# decoupling.net
KiCad netlist of a schematic drawn in Altium Designer
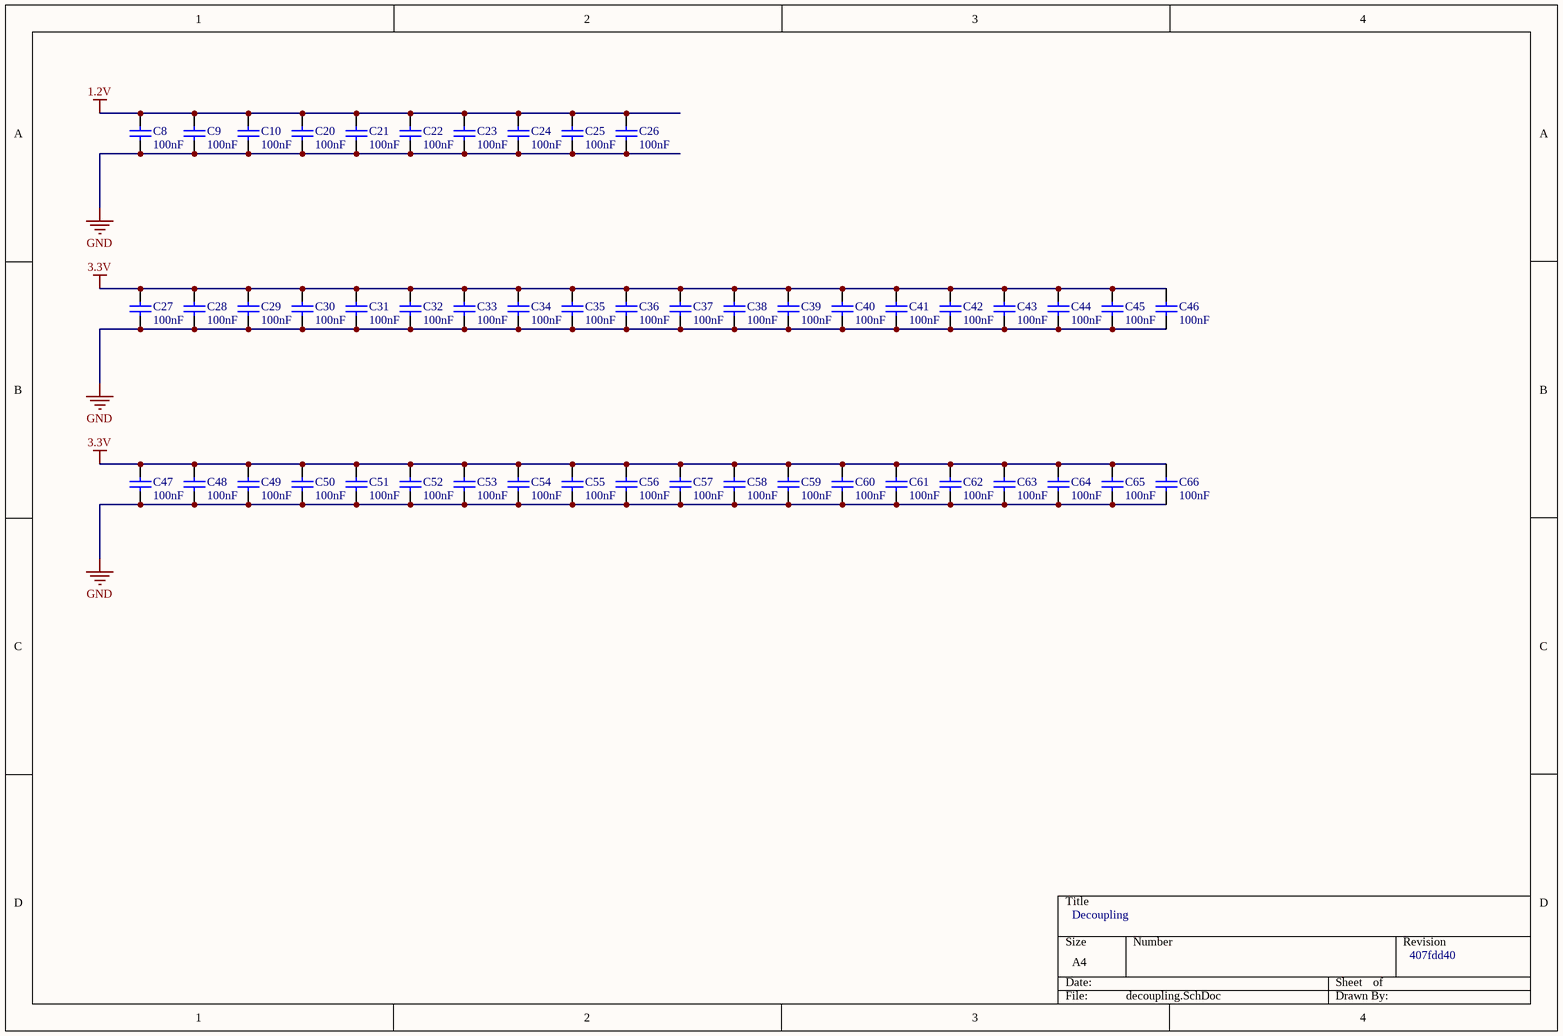
[diagram p0: decoupling.SchDoc]

(export (version "E")
  (design (tool "Eeschema 10.0.6"))
  (components
    (comp (ref "C8")
      (value "100nF")
      (footprint "CAPC1210(3225)100_L")
      (description "CAP 100nF 100V ±0.25pF 1210 (3225 Metric) Thickness 1mm SMD")
      (fields (field (name "TOLERANCE") "±0.25pF") (field (name "Comment") "CAP 10pF 100V 1210(3225)"))
      (libsource (lib "Altium Content Vault") (part "CMP-1038-00005-1"))
    )
    (comp (ref "C9")
      (value "100nF")
      (footprint "CAPC1210(3225)100_L")
      (description "CAP 100nF 100V ±0.25pF 1210 (3225 Metric) Thickness 1mm SMD")
      (fields (field (name "TOLERANCE") "±0.25pF") (field (name "Comment") "CAP 10pF 100V 1210(3225)"))
      (libsource (lib "Altium Content Vault") (part "CMP-1038-00005-1"))
    )
    (comp (ref "C10")
      (value "100nF")
      (footprint "CAPC1210(3225)100_L")
      (description "CAP 100nF 100V ±0.25pF 1210 (3225 Metric) Thickness 1mm SMD")
      (fields (field (name "TOLERANCE") "±0.25pF") (field (name "Comment") "CAP 10pF 100V 1210(3225)"))
      (libsource (lib "Altium Content Vault") (part "CMP-1038-00005-1"))
    )
    (comp (ref "C20")
      (value "100nF")
      (footprint "CAPC1210(3225)100_L")
      (description "CAP 100nF 100V ±0.25pF 1210 (3225 Metric) Thickness 1mm SMD")
      (fields (field (name "TOLERANCE") "±0.25pF") (field (name "Comment") "CAP 100nF 100V 1210(3225)"))
      (libsource (lib "Altium Content Vault") (part "CMP-1038-00005-1"))
    )
    (comp (ref "C21")
      (value "100nF")
      (footprint "CAPC1210(3225)100_L")
      (description "CAP 100nF 100V ±0.25pF 1210 (3225 Metric) Thickness 1mm SMD")
      (fields (field (name "TOLERANCE") "±0.25pF") (field (name "Comment") "CAP 100nF 100V 1210(3225)"))
      (libsource (lib "Altium Content Vault") (part "CMP-1038-00005-1"))
    )
    (comp (ref "C22")
      (value "100nF")
      (footprint "CAPC1210(3225)100_L")
      (description "CAP 100nF 100V ±0.25pF 1210 (3225 Metric) Thickness 1mm SMD")
      (fields (field (name "TOLERANCE") "±0.25pF") (field (name "Comment") "CAP 100nF 100V 1210(3225)"))
      (libsource (lib "Altium Content Vault") (part "CMP-1038-00005-1"))
    )
    (comp (ref "C23")
      (value "100nF")
      (footprint "CAPC1210(3225)100_L")
      (description "CAP 100nF 100V ±0.25pF 1210 (3225 Metric) Thickness 1mm SMD")
      (fields (field (name "TOLERANCE") "±0.25pF") (field (name "Comment") "CAP 100nF 100V 1210(3225)"))
      (libsource (lib "Altium Content Vault") (part "CMP-1038-00005-1"))
    )
    (comp (ref "C24")
      (value "100nF")
      (footprint "CAPC1210(3225)100_L")
      (description "CAP 100nF 100V ±0.25pF 1210 (3225 Metric) Thickness 1mm SMD")
      (fields (field (name "TOLERANCE") "±0.25pF") (field (name "Comment") "CAP 100nF 100V 1210(3225)"))
      (libsource (lib "Altium Content Vault") (part "CMP-1038-00005-1"))
    )
    (comp (ref "C25")
      (value "100nF")
      (footprint "CAPC1210(3225)100_L")
      (description "CAP 100nF 100V ±0.25pF 1210 (3225 Metric) Thickness 1mm SMD")
      (fields (field (name "TOLERANCE") "±0.25pF") (field (name "Comment") "CAP 100nF 100V 1210(3225)"))
      (libsource (lib "Altium Content Vault") (part "CMP-1038-00005-1"))
    )
    (comp (ref "C26")
      (value "100nF")
      (footprint "CAPC1210(3225)100_L")
      (description "CAP 100nF 100V ±0.25pF 1210 (3225 Metric) Thickness 1mm SMD")
      (fields (field (name "TOLERANCE") "±0.25pF") (field (name "Comment") "CAP 100nF 100V 1210(3225)"))
      (libsource (lib "Altium Content Vault") (part "CMP-1038-00005-1"))
    )
    (comp (ref "C27")
      (value "100nF")
      (footprint "CAPC1210(3225)100_L")
      (description "CAP 100nF 100V ±0.25pF 1210 (3225 Metric) Thickness 1mm SMD")
      (fields (field (name "TOLERANCE") "±0.25pF") (field (name "Comment") "CAP 100nF 100V 1210(3225)"))
      (libsource (lib "Altium Content Vault") (part "CMP-1038-00005-1"))
    )
    (comp (ref "C28")
      (value "100nF")
      (footprint "CAPC1210(3225)100_L")
      (description "CAP 100nF 100V ±0.25pF 1210 (3225 Metric) Thickness 1mm SMD")
      (fields (field (name "TOLERANCE") "±0.25pF") (field (name "Comment") "CAP 100nF 100V 1210(3225)"))
      (libsource (lib "Altium Content Vault") (part "CMP-1038-00005-1"))
    )
    (comp (ref "C29")
      (value "100nF")
      (footprint "CAPC1210(3225)100_L")
      (description "CAP 100nF 100V ±0.25pF 1210 (3225 Metric) Thickness 1mm SMD")
      (fields (field (name "TOLERANCE") "±0.25pF") (field (name "Comment") "CAP 100nF 100V 1210(3225)"))
      (libsource (lib "Altium Content Vault") (part "CMP-1038-00005-1"))
    )
    (comp (ref "C30")
      (value "100nF")
      (footprint "CAPC1210(3225)100_L")
      (description "CAP 100nF 100V ±0.25pF 1210 (3225 Metric) Thickness 1mm SMD")
      (fields (field (name "TOLERANCE") "±0.25pF") (field (name "Comment") "CAP 100nF 100V 1210(3225)"))
      (libsource (lib "Altium Content Vault") (part "CMP-1038-00005-1"))
    )
    (comp (ref "C31")
      (value "100nF")
      (footprint "CAPC1210(3225)100_L")
      (description "CAP 100nF 100V ±0.25pF 1210 (3225 Metric) Thickness 1mm SMD")
      (fields (field (name "TOLERANCE") "±0.25pF") (field (name "Comment") "CAP 100nF 100V 1210(3225)"))
      (libsource (lib "Altium Content Vault") (part "CMP-1038-00005-1"))
    )
    (comp (ref "C32")
      (value "100nF")
      (footprint "CAPC1210(3225)100_L")
      (description "CAP 100nF 100V ±0.25pF 1210 (3225 Metric) Thickness 1mm SMD")
      (fields (field (name "TOLERANCE") "±0.25pF") (field (name "Comment") "CAP 100nF 100V 1210(3225)"))
      (libsource (lib "Altium Content Vault") (part "CMP-1038-00005-1"))
    )
    (comp (ref "C33")
      (value "100nF")
      (footprint "CAPC1210(3225)100_L")
      (description "CAP 100nF 100V ±0.25pF 1210 (3225 Metric) Thickness 1mm SMD")
      (fields (field (name "TOLERANCE") "±0.25pF") (field (name "Comment") "CAP 100nF 100V 1210(3225)"))
      (libsource (lib "Altium Content Vault") (part "CMP-1038-00005-1"))
    )
    (comp (ref "C34")
      (value "100nF")
      (footprint "CAPC1210(3225)100_L")
      (description "CAP 100nF 100V ±0.25pF 1210 (3225 Metric) Thickness 1mm SMD")
      (fields (field (name "TOLERANCE") "±0.25pF") (field (name "Comment") "CAP 100nF 100V 1210(3225)"))
      (libsource (lib "Altium Content Vault") (part "CMP-1038-00005-1"))
    )
    (comp (ref "C35")
      (value "100nF")
      (footprint "CAPC1210(3225)100_L")
      (description "CAP 100nF 100V ±0.25pF 1210 (3225 Metric) Thickness 1mm SMD")
      (fields (field (name "TOLERANCE") "±0.25pF") (field (name "Comment") "CAP 100nF 100V 1210(3225)"))
      (libsource (lib "Altium Content Vault") (part "CMP-1038-00005-1"))
    )
    (comp (ref "C36")
      (value "100nF")
      (footprint "CAPC1210(3225)100_L")
      (description "CAP 100nF 100V ±0.25pF 1210 (3225 Metric) Thickness 1mm SMD")
      (fields (field (name "TOLERANCE") "±0.25pF") (field (name "Comment") "CAP 100nF 100V 1210(3225)"))
      (libsource (lib "Altium Content Vault") (part "CMP-1038-00005-1"))
    )
    (comp (ref "C37")
      (value "100nF")
      (footprint "CAPC1210(3225)100_L")
      (description "CAP 100nF 100V ±0.25pF 1210 (3225 Metric) Thickness 1mm SMD")
      (fields (field (name "TOLERANCE") "±0.25pF") (field (name "Comment") "CAP 100nF 100V 1210(3225)"))
      (libsource (lib "Altium Content Vault") (part "CMP-1038-00005-1"))
    )
    (comp (ref "C38")
      (value "100nF")
      (footprint "CAPC1210(3225)100_L")
      (description "CAP 100nF 100V ±0.25pF 1210 (3225 Metric) Thickness 1mm SMD")
      (fields (field (name "TOLERANCE") "±0.25pF") (field (name "Comment") "CAP 100nF 100V 1210(3225)"))
      (libsource (lib "Altium Content Vault") (part "CMP-1038-00005-1"))
    )
    (comp (ref "C39")
      (value "100nF")
      (footprint "CAPC1210(3225)100_L")
      (description "CAP 100nF 100V ±0.25pF 1210 (3225 Metric) Thickness 1mm SMD")
      (fields (field (name "TOLERANCE") "±0.25pF") (field (name "Comment") "CAP 100nF 100V 1210(3225)"))
      (libsource (lib "Altium Content Vault") (part "CMP-1038-00005-1"))
    )
    (comp (ref "C40")
      (value "100nF")
      (footprint "CAPC1210(3225)100_L")
      (description "CAP 100nF 100V ±0.25pF 1210 (3225 Metric) Thickness 1mm SMD")
      (fields (field (name "TOLERANCE") "±0.25pF") (field (name "Comment") "CAP 100nF 100V 1210(3225)"))
      (libsource (lib "Altium Content Vault") (part "CMP-1038-00005-1"))
    )
    (comp (ref "C41")
      (value "100nF")
      (footprint "CAPC1210(3225)100_L")
      (description "CAP 100nF 100V ±0.25pF 1210 (3225 Metric) Thickness 1mm SMD")
      (fields (field (name "TOLERANCE") "±0.25pF") (field (name "Comment") "CAP 100nF 100V 1210(3225)"))
      (libsource (lib "Altium Content Vault") (part "CMP-1038-00005-1"))
    )
    (comp (ref "C42")
      (value "100nF")
      (footprint "CAPC1210(3225)100_L")
      (description "CAP 100nF 100V ±0.25pF 1210 (3225 Metric) Thickness 1mm SMD")
      (fields (field (name "TOLERANCE") "±0.25pF") (field (name "Comment") "CAP 100nF 100V 1210(3225)"))
      (libsource (lib "Altium Content Vault") (part "CMP-1038-00005-1"))
    )
    (comp (ref "C43")
      (value "100nF")
      (footprint "CAPC1210(3225)100_L")
      (description "CAP 100nF 100V ±0.25pF 1210 (3225 Metric) Thickness 1mm SMD")
      (fields (field (name "TOLERANCE") "±0.25pF") (field (name "Comment") "CAP 100nF 100V 1210(3225)"))
      (libsource (lib "Altium Content Vault") (part "CMP-1038-00005-1"))
    )
    (comp (ref "C44")
      (value "100nF")
      (footprint "CAPC1210(3225)100_L")
      (description "CAP 100nF 100V ±0.25pF 1210 (3225 Metric) Thickness 1mm SMD")
      (fields (field (name "TOLERANCE") "±0.25pF") (field (name "Comment") "CAP 100nF 100V 1210(3225)"))
      (libsource (lib "Altium Content Vault") (part "CMP-1038-00005-1"))
    )
    (comp (ref "C45")
      (value "100nF")
      (footprint "CAPC1210(3225)100_L")
      (description "CAP 100nF 100V ±0.25pF 1210 (3225 Metric) Thickness 1mm SMD")
      (fields (field (name "TOLERANCE") "±0.25pF") (field (name "Comment") "CAP 100nF 100V 1210(3225)"))
      (libsource (lib "Altium Content Vault") (part "CMP-1038-00005-1"))
    )
    (comp (ref "C46")
      (value "100nF")
      (footprint "CAPC1210(3225)100_L")
      (description "CAP 100nF 100V ±0.25pF 1210 (3225 Metric) Thickness 1mm SMD")
      (fields (field (name "TOLERANCE") "±0.25pF") (field (name "Comment") "CAP 100nF 100V 1210(3225)"))
      (libsource (lib "Altium Content Vault") (part "CMP-1038-00005-1"))
    )
    (comp (ref "C47")
      (value "100nF")
      (footprint "CAPC1210(3225)100_L")
      (description "CAP 100nF 100V ±0.25pF 1210 (3225 Metric) Thickness 1mm SMD")
      (fields (field (name "TOLERANCE") "±0.25pF") (field (name "Comment") "CAP 100nF 100V 1210(3225)"))
      (libsource (lib "Altium Content Vault") (part "CMP-1038-00005-1"))
    )
    (comp (ref "C48")
      (value "100nF")
      (footprint "CAPC1210(3225)100_L")
      (description "CAP 100nF 100V ±0.25pF 1210 (3225 Metric) Thickness 1mm SMD")
      (fields (field (name "TOLERANCE") "±0.25pF") (field (name "Comment") "CAP 100nF 100V 1210(3225)"))
      (libsource (lib "Altium Content Vault") (part "CMP-1038-00005-1"))
    )
    (comp (ref "C49")
      (value "100nF")
      (footprint "CAPC1210(3225)100_L")
      (description "CAP 100nF 100V ±0.25pF 1210 (3225 Metric) Thickness 1mm SMD")
      (fields (field (name "TOLERANCE") "±0.25pF") (field (name "Comment") "CAP 100nF 100V 1210(3225)"))
      (libsource (lib "Altium Content Vault") (part "CMP-1038-00005-1"))
    )
    (comp (ref "C50")
      (value "100nF")
      (footprint "CAPC1210(3225)100_L")
      (description "CAP 100nF 100V ±0.25pF 1210 (3225 Metric) Thickness 1mm SMD")
      (fields (field (name "TOLERANCE") "±0.25pF") (field (name "Comment") "CAP 100nF 100V 1210(3225)"))
      (libsource (lib "Altium Content Vault") (part "CMP-1038-00005-1"))
    )
    (comp (ref "C51")
      (value "100nF")
      (footprint "CAPC1210(3225)100_L")
      (description "CAP 100nF 100V ±0.25pF 1210 (3225 Metric) Thickness 1mm SMD")
      (fields (field (name "TOLERANCE") "±0.25pF") (field (name "Comment") "CAP 100nF 100V 1210(3225)"))
      (libsource (lib "Altium Content Vault") (part "CMP-1038-00005-1"))
    )
    (comp (ref "C52")
      (value "100nF")
      (footprint "CAPC1210(3225)100_L")
      (description "CAP 100nF 100V ±0.25pF 1210 (3225 Metric) Thickness 1mm SMD")
      (fields (field (name "TOLERANCE") "±0.25pF") (field (name "Comment") "CAP 100nF 100V 1210(3225)"))
      (libsource (lib "Altium Content Vault") (part "CMP-1038-00005-1"))
    )
    (comp (ref "C53")
      (value "100nF")
      (footprint "CAPC1210(3225)100_L")
      (description "CAP 100nF 100V ±0.25pF 1210 (3225 Metric) Thickness 1mm SMD")
      (fields (field (name "TOLERANCE") "±0.25pF") (field (name "Comment") "CAP 100nF 100V 1210(3225)"))
      (libsource (lib "Altium Content Vault") (part "CMP-1038-00005-1"))
    )
    (comp (ref "C54")
      (value "100nF")
      (footprint "CAPC1210(3225)100_L")
      (description "CAP 100nF 100V ±0.25pF 1210 (3225 Metric) Thickness 1mm SMD")
      (fields (field (name "TOLERANCE") "±0.25pF") (field (name "Comment") "CAP 100nF 100V 1210(3225)"))
      (libsource (lib "Altium Content Vault") (part "CMP-1038-00005-1"))
    )
    (comp (ref "C55")
      (value "100nF")
      (footprint "CAPC1210(3225)100_L")
      (description "CAP 100nF 100V ±0.25pF 1210 (3225 Metric) Thickness 1mm SMD")
      (fields (field (name "TOLERANCE") "±0.25pF") (field (name "Comment") "CAP 100nF 100V 1210(3225)"))
      (libsource (lib "Altium Content Vault") (part "CMP-1038-00005-1"))
    )
    (comp (ref "C56")
      (value "100nF")
      (footprint "CAPC1210(3225)100_L")
      (description "CAP 100nF 100V ±0.25pF 1210 (3225 Metric) Thickness 1mm SMD")
      (fields (field (name "TOLERANCE") "±0.25pF") (field (name "Comment") "CAP 100nF 100V 1210(3225)"))
      (libsource (lib "Altium Content Vault") (part "CMP-1038-00005-1"))
    )
    (comp (ref "C57")
      (value "100nF")
      (footprint "CAPC1210(3225)100_L")
      (description "CAP 100nF 100V ±0.25pF 1210 (3225 Metric) Thickness 1mm SMD")
      (fields (field (name "TOLERANCE") "±0.25pF") (field (name "Comment") "CAP 100nF 100V 1210(3225)"))
      (libsource (lib "Altium Content Vault") (part "CMP-1038-00005-1"))
    )
    (comp (ref "C58")
      (value "100nF")
      (footprint "CAPC1210(3225)100_L")
      (description "CAP 100nF 100V ±0.25pF 1210 (3225 Metric) Thickness 1mm SMD")
      (fields (field (name "TOLERANCE") "±0.25pF") (field (name "Comment") "CAP 100nF 100V 1210(3225)"))
      (libsource (lib "Altium Content Vault") (part "CMP-1038-00005-1"))
    )
    (comp (ref "C59")
      (value "100nF")
      (footprint "CAPC1210(3225)100_L")
      (description "CAP 100nF 100V ±0.25pF 1210 (3225 Metric) Thickness 1mm SMD")
      (fields (field (name "TOLERANCE") "±0.25pF") (field (name "Comment") "CAP 100nF 100V 1210(3225)"))
      (libsource (lib "Altium Content Vault") (part "CMP-1038-00005-1"))
    )
    (comp (ref "C60")
      (value "100nF")
      (footprint "CAPC1210(3225)100_L")
      (description "CAP 100nF 100V ±0.25pF 1210 (3225 Metric) Thickness 1mm SMD")
      (fields (field (name "TOLERANCE") "±0.25pF") (field (name "Comment") "CAP 100nF 100V 1210(3225)"))
      (libsource (lib "Altium Content Vault") (part "CMP-1038-00005-1"))
    )
    (comp (ref "C61")
      (value "100nF")
      (footprint "CAPC1210(3225)100_L")
      (description "CAP 100nF 100V ±0.25pF 1210 (3225 Metric) Thickness 1mm SMD")
      (fields (field (name "TOLERANCE") "±0.25pF") (field (name "Comment") "CAP 100nF 100V 1210(3225)"))
      (libsource (lib "Altium Content Vault") (part "CMP-1038-00005-1"))
    )
    (comp (ref "C62")
      (value "100nF")
      (footprint "CAPC1210(3225)100_L")
      (description "CAP 100nF 100V ±0.25pF 1210 (3225 Metric) Thickness 1mm SMD")
      (fields (field (name "TOLERANCE") "±0.25pF") (field (name "Comment") "CAP 100nF 100V 1210(3225)"))
      (libsource (lib "Altium Content Vault") (part "CMP-1038-00005-1"))
    )
    (comp (ref "C63")
      (value "100nF")
      (footprint "CAPC1210(3225)100_L")
      (description "CAP 100nF 100V ±0.25pF 1210 (3225 Metric) Thickness 1mm SMD")
      (fields (field (name "TOLERANCE") "±0.25pF") (field (name "Comment") "CAP 100nF 100V 1210(3225)"))
      (libsource (lib "Altium Content Vault") (part "CMP-1038-00005-1"))
    )
    (comp (ref "C64")
      (value "100nF")
      (footprint "CAPC1210(3225)100_L")
      (description "CAP 100nF 100V ±0.25pF 1210 (3225 Metric) Thickness 1mm SMD")
      (fields (field (name "TOLERANCE") "±0.25pF") (field (name "Comment") "CAP 100nF 100V 1210(3225)"))
      (libsource (lib "Altium Content Vault") (part "CMP-1038-00005-1"))
    )
    (comp (ref "C65")
      (value "100nF")
      (footprint "CAPC1210(3225)100_L")
      (description "CAP 100nF 100V ±0.25pF 1210 (3225 Metric) Thickness 1mm SMD")
      (fields (field (name "TOLERANCE") "±0.25pF") (field (name "Comment") "CAP 100nF 100V 1210(3225)"))
      (libsource (lib "Altium Content Vault") (part "CMP-1038-00005-1"))
    )
    (comp (ref "C66")
      (value "100nF")
      (footprint "CAPC1210(3225)100_L")
      (description "CAP 100nF 100V ±0.25pF 1210 (3225 Metric) Thickness 1mm SMD")
      (fields (field (name "TOLERANCE") "±0.25pF") (field (name "Comment") "CAP 100nF 100V 1210(3225)"))
      (libsource (lib "Altium Content Vault") (part "CMP-1038-00005-1"))
    )
  )
  (nets
    (net (code "1") (name "1.2V") (class "Default")
      (node (ref "C10") (pin "1") (pinfunction "1_1") (pintype "passive"))
      (node (ref "C20") (pin "1") (pinfunction "1_1") (pintype "passive"))
      (node (ref "C21") (pin "1") (pinfunction "1_1") (pintype "passive"))
      (node (ref "C22") (pin "1") (pinfunction "1_1") (pintype "passive"))
      (node (ref "C23") (pin "1") (pinfunction "1_1") (pintype "passive"))
      (node (ref "C24") (pin "1") (pinfunction "1_1") (pintype "passive"))
      (node (ref "C25") (pin "1") (pinfunction "1_1") (pintype "passive"))
      (node (ref "C26") (pin "1") (pinfunction "1_1") (pintype "passive"))
      (node (ref "C8") (pin "1") (pinfunction "1_1") (pintype "passive"))
      (node (ref "C9") (pin "1") (pinfunction "1_1") (pintype "passive"))
    )
    (net (code "2") (name "3.3V") (class "Default")
      (node (ref "C27") (pin "1") (pinfunction "1_1") (pintype "passive"))
      (node (ref "C28") (pin "1") (pinfunction "1_1") (pintype "passive"))
      (node (ref "C29") (pin "1") (pinfunction "1_1") (pintype "passive"))
      (node (ref "C30") (pin "1") (pinfunction "1_1") (pintype "passive"))
      (node (ref "C31") (pin "1") (pinfunction "1_1") (pintype "passive"))
      (node (ref "C32") (pin "1") (pinfunction "1_1") (pintype "passive"))
      (node (ref "C33") (pin "1") (pinfunction "1_1") (pintype "passive"))
      (node (ref "C34") (pin "1") (pinfunction "1_1") (pintype "passive"))
      (node (ref "C35") (pin "1") (pinfunction "1_1") (pintype "passive"))
      (node (ref "C36") (pin "1") (pinfunction "1_1") (pintype "passive"))
      (node (ref "C37") (pin "1") (pinfunction "1_1") (pintype "passive"))
      (node (ref "C38") (pin "1") (pinfunction "1_1") (pintype "passive"))
      (node (ref "C39") (pin "1") (pinfunction "1_1") (pintype "passive"))
      (node (ref "C40") (pin "1") (pinfunction "1_1") (pintype "passive"))
      (node (ref "C41") (pin "1") (pinfunction "1_1") (pintype "passive"))
      (node (ref "C42") (pin "1") (pinfunction "1_1") (pintype "passive"))
      (node (ref "C43") (pin "1") (pinfunction "1_1") (pintype "passive"))
      (node (ref "C44") (pin "1") (pinfunction "1_1") (pintype "passive"))
      (node (ref "C45") (pin "1") (pinfunction "1_1") (pintype "passive"))
      (node (ref "C46") (pin "1") (pinfunction "1_1") (pintype "passive"))
      (node (ref "C47") (pin "1") (pinfunction "1_1") (pintype "passive"))
      (node (ref "C48") (pin "1") (pinfunction "1_1") (pintype "passive"))
      (node (ref "C49") (pin "1") (pinfunction "1_1") (pintype "passive"))
      (node (ref "C50") (pin "1") (pinfunction "1_1") (pintype "passive"))
      (node (ref "C51") (pin "1") (pinfunction "1_1") (pintype "passive"))
      (node (ref "C52") (pin "1") (pinfunction "1_1") (pintype "passive"))
      (node (ref "C53") (pin "1") (pinfunction "1_1") (pintype "passive"))
      (node (ref "C54") (pin "1") (pinfunction "1_1") (pintype "passive"))
      (node (ref "C55") (pin "1") (pinfunction "1_1") (pintype "passive"))
      (node (ref "C56") (pin "1") (pinfunction "1_1") (pintype "passive"))
      (node (ref "C57") (pin "1") (pinfunction "1_1") (pintype "passive"))
      (node (ref "C58") (pin "1") (pinfunction "1_1") (pintype "passive"))
      (node (ref "C59") (pin "1") (pinfunction "1_1") (pintype "passive"))
      (node (ref "C60") (pin "1") (pinfunction "1_1") (pintype "passive"))
      (node (ref "C61") (pin "1") (pinfunction "1_1") (pintype "passive"))
      (node (ref "C62") (pin "1") (pinfunction "1_1") (pintype "passive"))
      (node (ref "C63") (pin "1") (pinfunction "1_1") (pintype "passive"))
      (node (ref "C64") (pin "1") (pinfunction "1_1") (pintype "passive"))
      (node (ref "C65") (pin "1") (pinfunction "1_1") (pintype "passive"))
      (node (ref "C66") (pin "1") (pinfunction "1_1") (pintype "passive"))
    )
    (net (code "3") (name "GND") (class "Default")
      (node (ref "C10") (pin "2") (pinfunction "2_2") (pintype "passive"))
      (node (ref "C20") (pin "2") (pinfunction "2_2") (pintype "passive"))
      (node (ref "C21") (pin "2") (pinfunction "2_2") (pintype "passive"))
      (node (ref "C22") (pin "2") (pinfunction "2_2") (pintype "passive"))
      (node (ref "C23") (pin "2") (pinfunction "2_2") (pintype "passive"))
      (node (ref "C24") (pin "2") (pinfunction "2_2") (pintype "passive"))
      (node (ref "C25") (pin "2") (pinfunction "2_2") (pintype "passive"))
      (node (ref "C26") (pin "2") (pinfunction "2_2") (pintype "passive"))
      (node (ref "C27") (pin "2") (pinfunction "2_2") (pintype "passive"))
      (node (ref "C28") (pin "2") (pinfunction "2_2") (pintype "passive"))
      (node (ref "C29") (pin "2") (pinfunction "2_2") (pintype "passive"))
      (node (ref "C30") (pin "2") (pinfunction "2_2") (pintype "passive"))
      (node (ref "C31") (pin "2") (pinfunction "2_2") (pintype "passive"))
      (node (ref "C32") (pin "2") (pinfunction "2_2") (pintype "passive"))
      (node (ref "C33") (pin "2") (pinfunction "2_2") (pintype "passive"))
      (node (ref "C34") (pin "2") (pinfunction "2_2") (pintype "passive"))
      (node (ref "C35") (pin "2") (pinfunction "2_2") (pintype "passive"))
      (node (ref "C36") (pin "2") (pinfunction "2_2") (pintype "passive"))
      (node (ref "C37") (pin "2") (pinfunction "2_2") (pintype "passive"))
      (node (ref "C38") (pin "2") (pinfunction "2_2") (pintype "passive"))
      (node (ref "C39") (pin "2") (pinfunction "2_2") (pintype "passive"))
      (node (ref "C40") (pin "2") (pinfunction "2_2") (pintype "passive"))
      (node (ref "C41") (pin "2") (pinfunction "2_2") (pintype "passive"))
      (node (ref "C42") (pin "2") (pinfunction "2_2") (pintype "passive"))
      (node (ref "C43") (pin "2") (pinfunction "2_2") (pintype "passive"))
      (node (ref "C44") (pin "2") (pinfunction "2_2") (pintype "passive"))
      (node (ref "C45") (pin "2") (pinfunction "2_2") (pintype "passive"))
      (node (ref "C46") (pin "2") (pinfunction "2_2") (pintype "passive"))
      (node (ref "C47") (pin "2") (pinfunction "2_2") (pintype "passive"))
      (node (ref "C48") (pin "2") (pinfunction "2_2") (pintype "passive"))
      (node (ref "C49") (pin "2") (pinfunction "2_2") (pintype "passive"))
      (node (ref "C50") (pin "2") (pinfunction "2_2") (pintype "passive"))
      (node (ref "C51") (pin "2") (pinfunction "2_2") (pintype "passive"))
      (node (ref "C52") (pin "2") (pinfunction "2_2") (pintype "passive"))
      (node (ref "C53") (pin "2") (pinfunction "2_2") (pintype "passive"))
      (node (ref "C54") (pin "2") (pinfunction "2_2") (pintype "passive"))
      (node (ref "C55") (pin "2") (pinfunction "2_2") (pintype "passive"))
      (node (ref "C56") (pin "2") (pinfunction "2_2") (pintype "passive"))
      (node (ref "C57") (pin "2") (pinfunction "2_2") (pintype "passive"))
      (node (ref "C58") (pin "2") (pinfunction "2_2") (pintype "passive"))
      (node (ref "C59") (pin "2") (pinfunction "2_2") (pintype "passive"))
      (node (ref "C60") (pin "2") (pinfunction "2_2") (pintype "passive"))
      (node (ref "C61") (pin "2") (pinfunction "2_2") (pintype "passive"))
      (node (ref "C62") (pin "2") (pinfunction "2_2") (pintype "passive"))
      (node (ref "C63") (pin "2") (pinfunction "2_2") (pintype "passive"))
      (node (ref "C64") (pin "2") (pinfunction "2_2") (pintype "passive"))
      (node (ref "C65") (pin "2") (pinfunction "2_2") (pintype "passive"))
      (node (ref "C66") (pin "2") (pinfunction "2_2") (pintype "passive"))
      (node (ref "C8") (pin "2") (pinfunction "2_2") (pintype "passive"))
      (node (ref "C9") (pin "2") (pinfunction "2_2") (pintype "passive"))
    )
  )
)
